# SERVICES_1.net
KiCad netlist of a schematic drawn in EAGLE
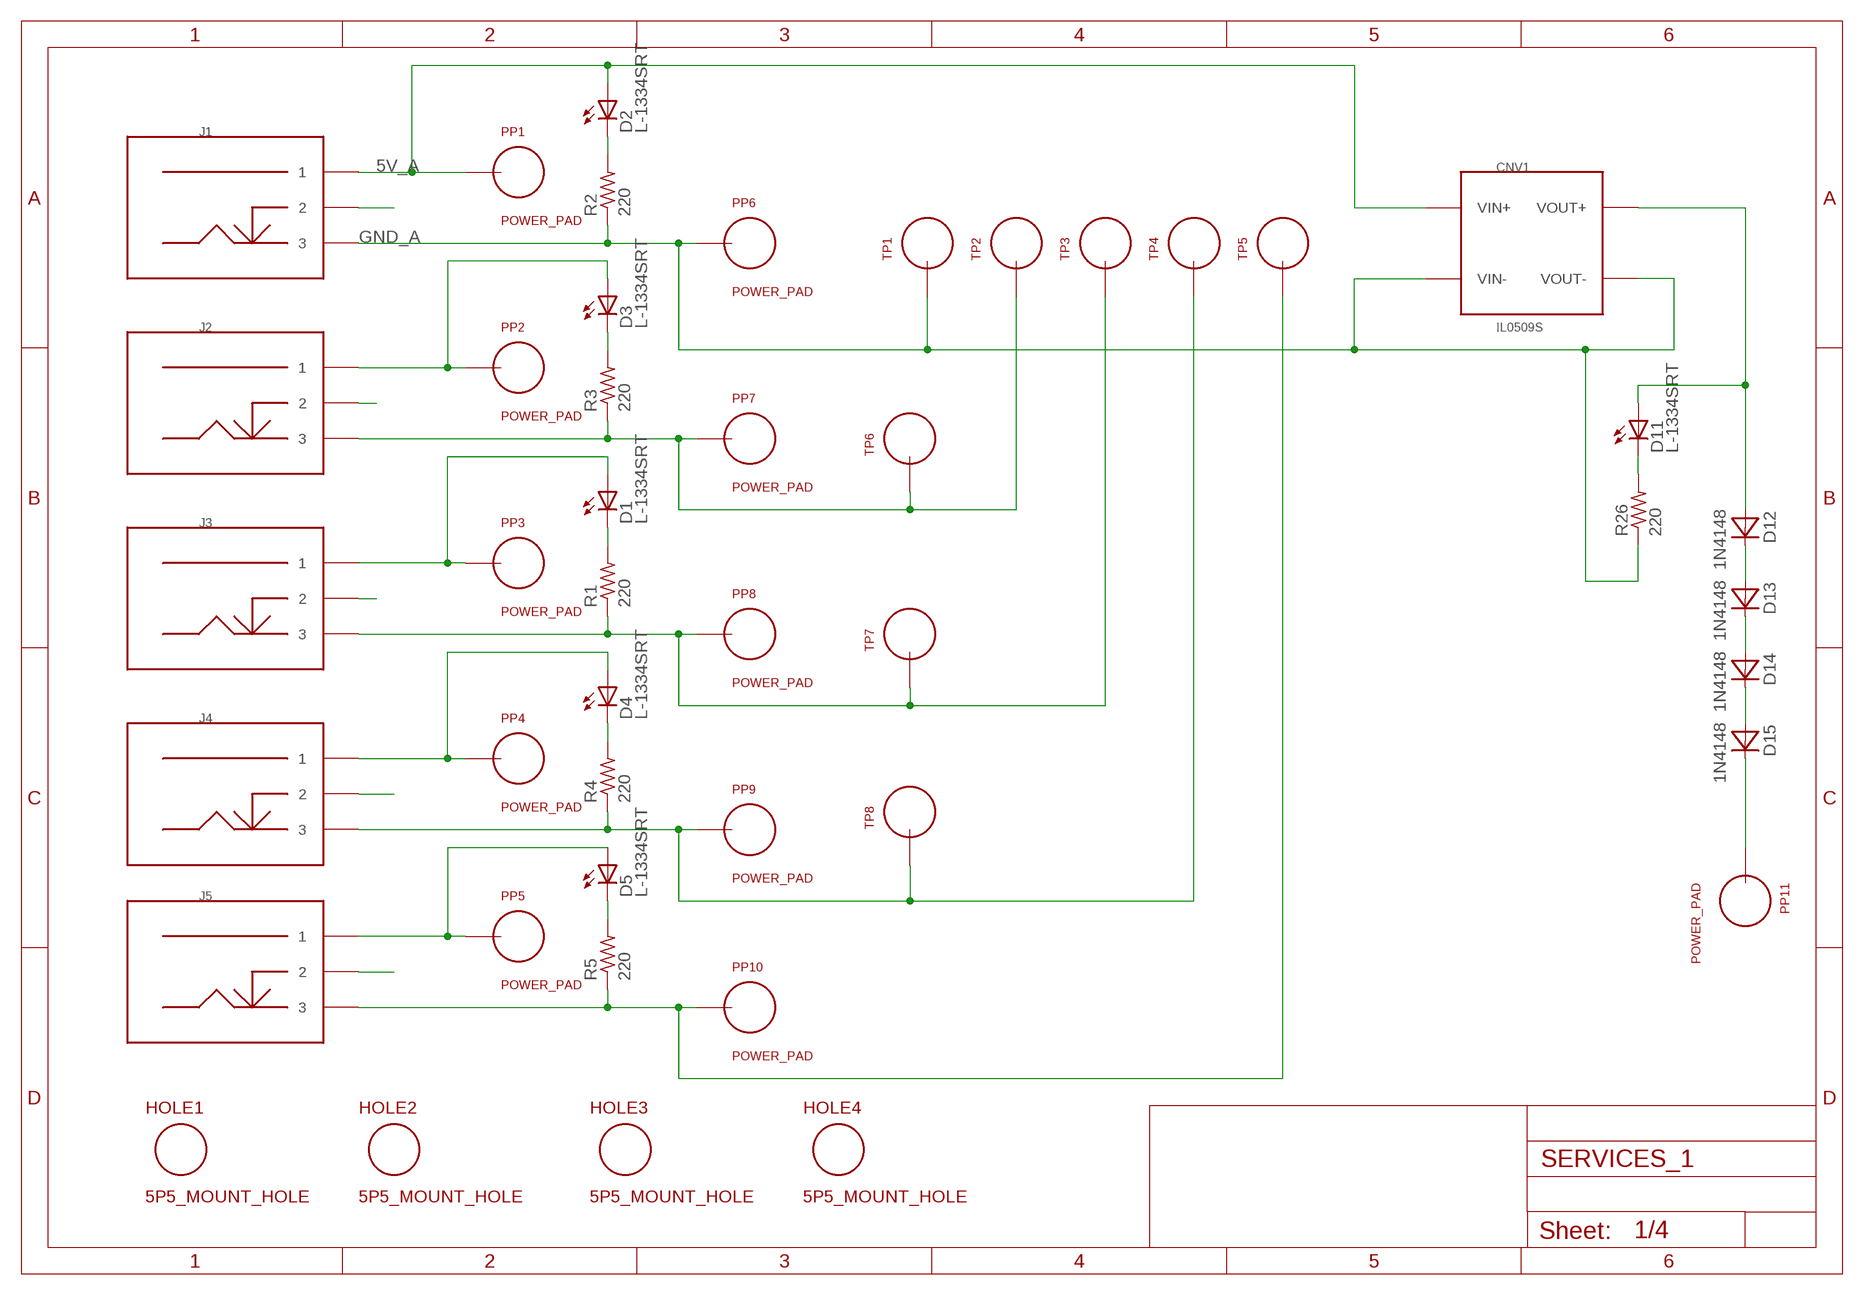
[diagram p0: schematic, sheet 1]
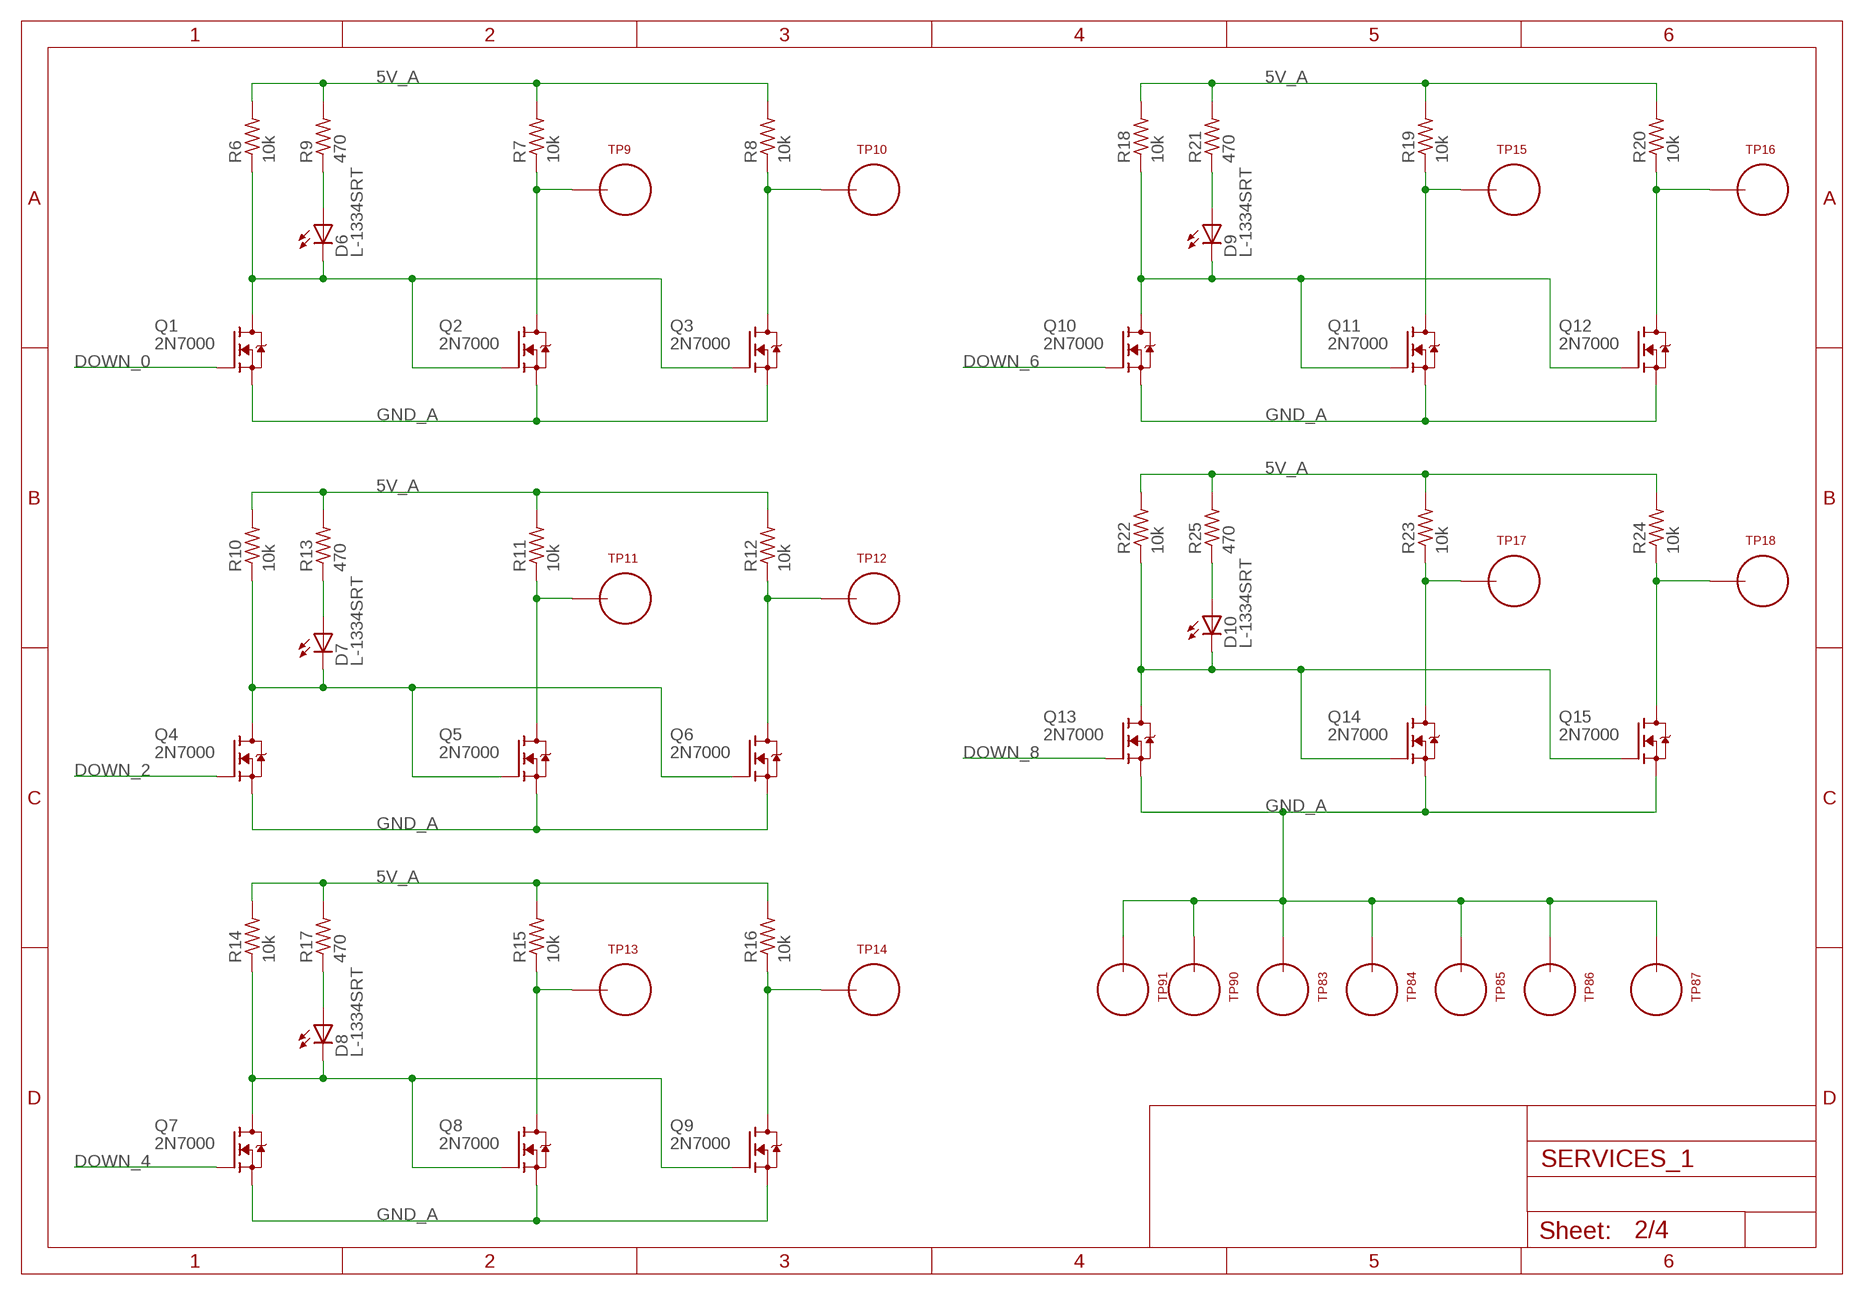
[diagram p1: schematic, sheet 2]
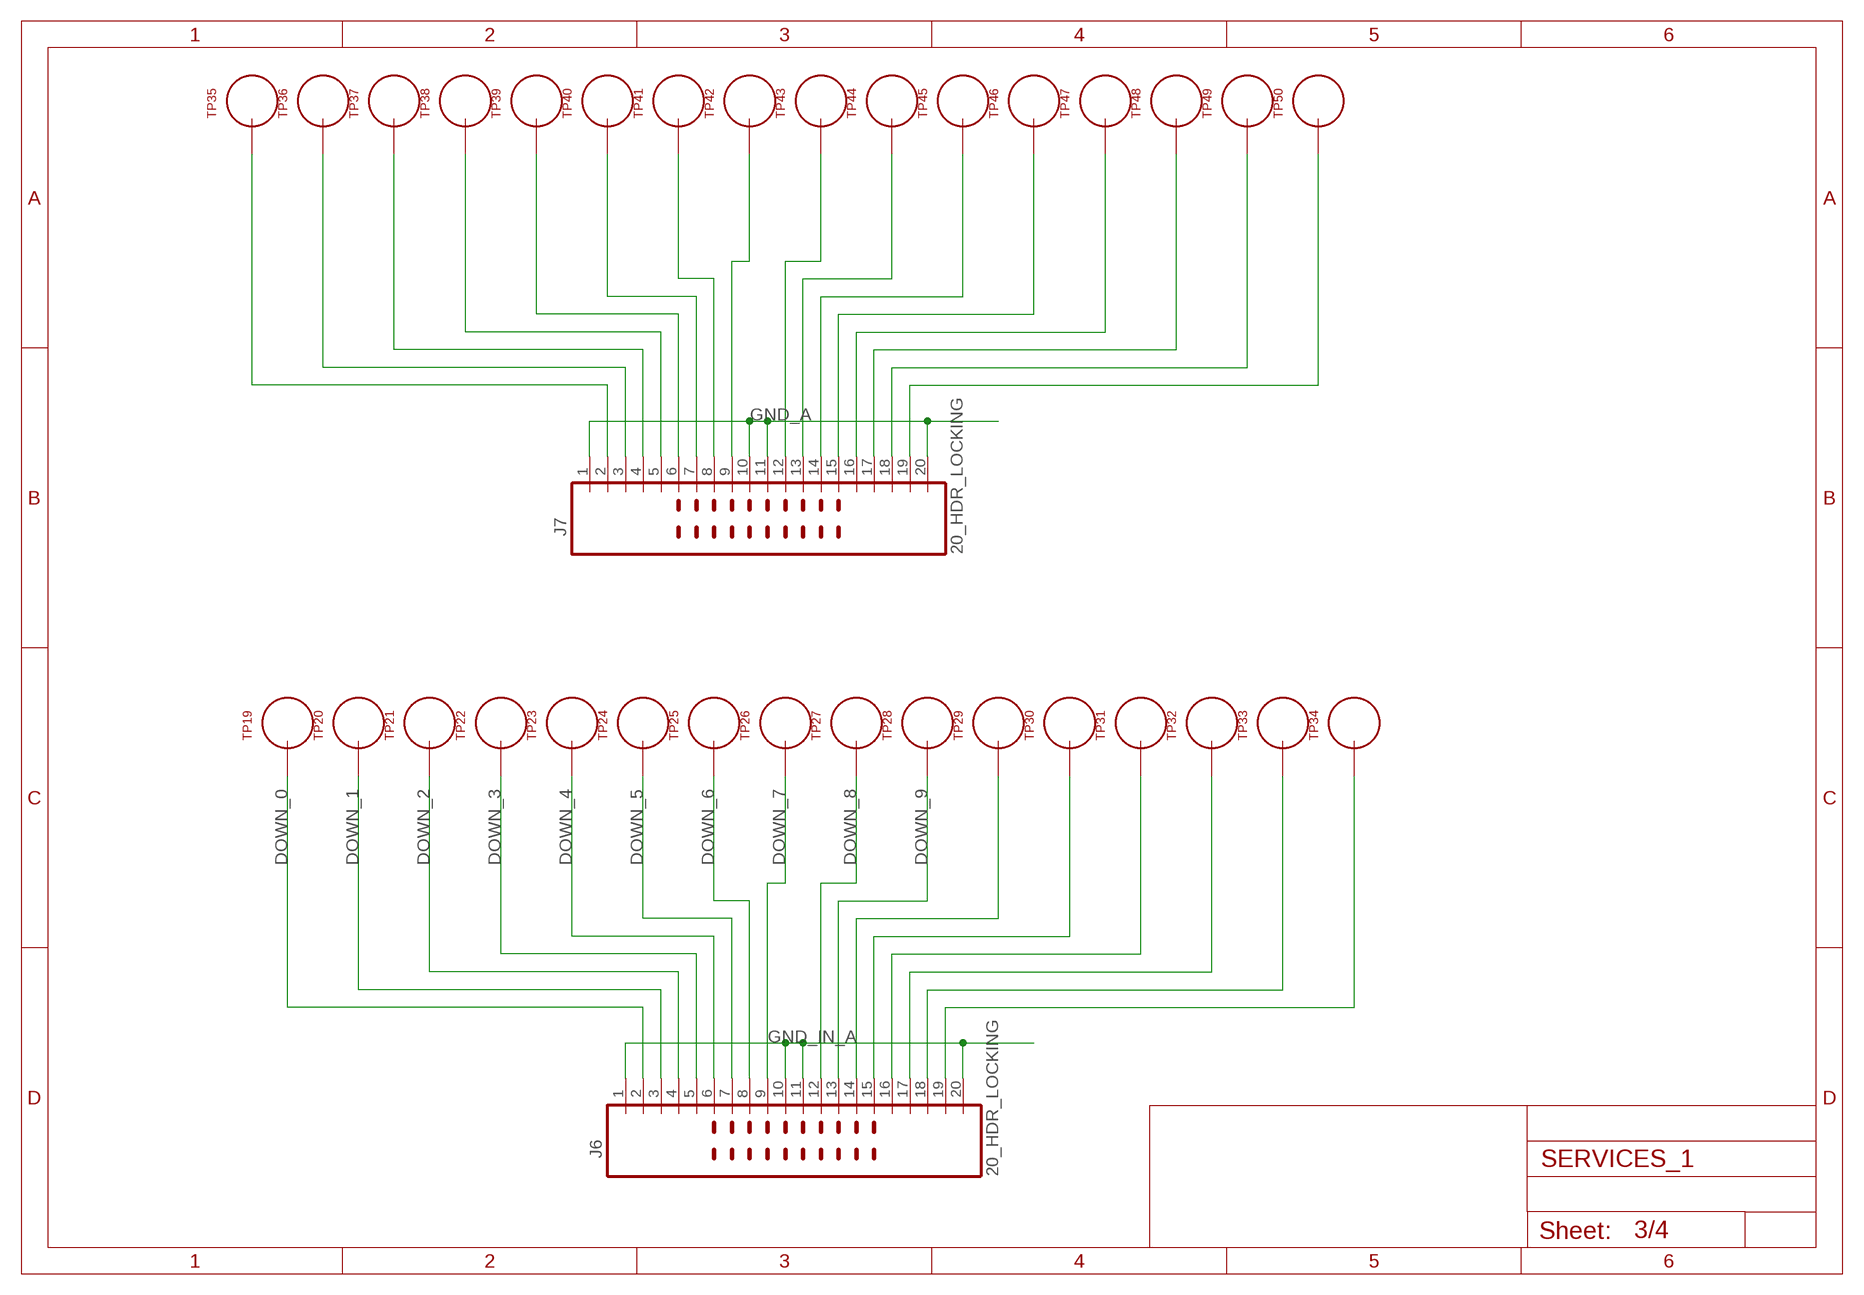
[diagram p2: schematic, sheet 3]
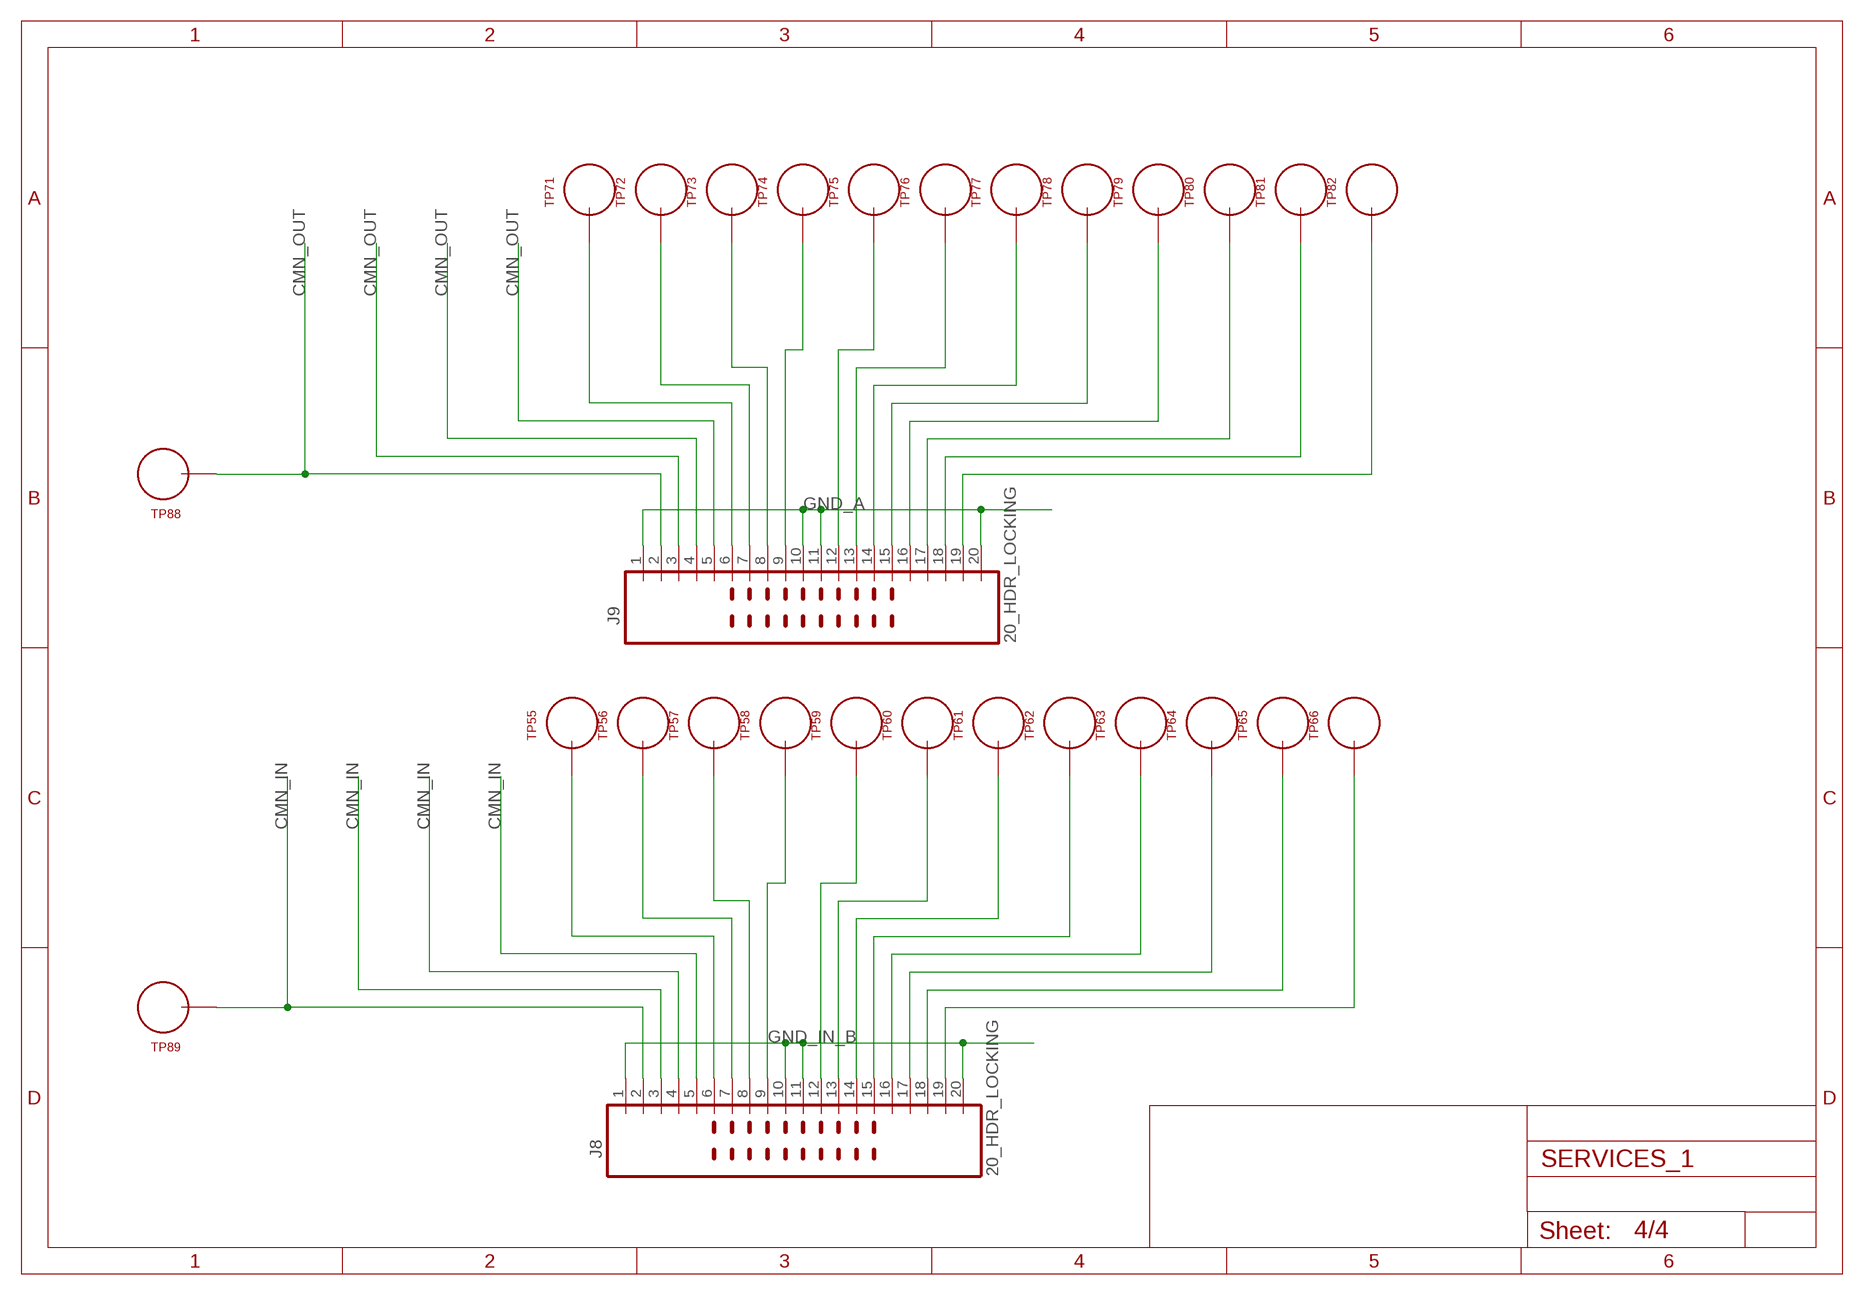
[diagram p3: schematic, sheet 4]

(export (version "E")
  (design (tool "Eeschema 10.0.6"))
  (components
    (comp (ref "D6")
      (value "L-1334SRT")
      (footprint "eagle-import:LED3MM")
      (libsource (lib "eagle-import") (part "L-1334SRT"))
    )
    (comp (ref "D7")
      (value "L-1334SRT")
      (footprint "eagle-import:LED3MM")
      (libsource (lib "eagle-import") (part "L-1334SRT"))
    )
    (comp (ref "D8")
      (value "L-1334SRT")
      (footprint "eagle-import:LED3MM")
      (libsource (lib "eagle-import") (part "L-1334SRT"))
    )
    (comp (ref "D9")
      (value "L-1334SRT")
      (footprint "eagle-import:LED3MM")
      (libsource (lib "eagle-import") (part "L-1334SRT"))
    )
    (comp (ref "D10")
      (value "L-1334SRT")
      (footprint "eagle-import:LED3MM")
      (libsource (lib "eagle-import") (part "L-1334SRT"))
    )
    (comp (ref "Q1")
      (value "2N7000")
      (footprint "eagle-import:TO92-DGS")
      (libsource (lib "eagle-import") (part "2N7000"))
    )
    (comp (ref "Q2")
      (value "2N7000")
      (footprint "eagle-import:TO92-DGS")
      (libsource (lib "eagle-import") (part "2N7000"))
    )
    (comp (ref "Q3")
      (value "2N7000")
      (footprint "eagle-import:TO92-DGS")
      (libsource (lib "eagle-import") (part "2N7000"))
    )
    (comp (ref "Q4")
      (value "2N7000")
      (footprint "eagle-import:TO92-DGS")
      (libsource (lib "eagle-import") (part "2N7000"))
    )
    (comp (ref "Q5")
      (value "2N7000")
      (footprint "eagle-import:TO92-DGS")
      (libsource (lib "eagle-import") (part "2N7000"))
    )
    (comp (ref "Q6")
      (value "2N7000")
      (footprint "eagle-import:TO92-DGS")
      (libsource (lib "eagle-import") (part "2N7000"))
    )
    (comp (ref "Q7")
      (value "2N7000")
      (footprint "eagle-import:TO92-DGS")
      (libsource (lib "eagle-import") (part "2N7000"))
    )
    (comp (ref "Q8")
      (value "2N7000")
      (footprint "eagle-import:TO92-DGS")
      (libsource (lib "eagle-import") (part "2N7000"))
    )
    (comp (ref "Q9")
      (value "2N7000")
      (footprint "eagle-import:TO92-DGS")
      (libsource (lib "eagle-import") (part "2N7000"))
    )
    (comp (ref "Q10")
      (value "2N7000")
      (footprint "eagle-import:TO92-DGS")
      (libsource (lib "eagle-import") (part "2N7000"))
    )
    (comp (ref "Q11")
      (value "2N7000")
      (footprint "eagle-import:TO92-DGS")
      (libsource (lib "eagle-import") (part "2N7000"))
    )
    (comp (ref "Q12")
      (value "2N7000")
      (footprint "eagle-import:TO92-DGS")
      (libsource (lib "eagle-import") (part "2N7000"))
    )
    (comp (ref "Q13")
      (value "2N7000")
      (footprint "eagle-import:TO92-DGS")
      (libsource (lib "eagle-import") (part "2N7000"))
    )
    (comp (ref "Q14")
      (value "2N7000")
      (footprint "eagle-import:TO92-DGS")
      (libsource (lib "eagle-import") (part "2N7000"))
    )
    (comp (ref "Q15")
      (value "2N7000")
      (footprint "eagle-import:TO92-DGS")
      (libsource (lib "eagle-import") (part "2N7000"))
    )
    (comp (ref "R6")
      (value "10k")
      (footprint "eagle-import:R_P2INCH")
      (libsource (lib "eagle-import") (part "R_P2INCH"))
    )
    (comp (ref "R7")
      (value "10k")
      (footprint "eagle-import:R_P2INCH")
      (libsource (lib "eagle-import") (part "R_P2INCH"))
    )
    (comp (ref "R8")
      (value "10k")
      (footprint "eagle-import:R_P2INCH")
      (libsource (lib "eagle-import") (part "R_P2INCH"))
    )
    (comp (ref "R9")
      (value "470")
      (footprint "eagle-import:R_P2INCH")
      (libsource (lib "eagle-import") (part "R_P2INCH"))
    )
    (comp (ref "R10")
      (value "10k")
      (footprint "eagle-import:R_P2INCH")
      (libsource (lib "eagle-import") (part "R_P2INCH"))
    )
    (comp (ref "R11")
      (value "10k")
      (footprint "eagle-import:R_P2INCH")
      (libsource (lib "eagle-import") (part "R_P2INCH"))
    )
    (comp (ref "R12")
      (value "10k")
      (footprint "eagle-import:R_P2INCH")
      (libsource (lib "eagle-import") (part "R_P2INCH"))
    )
    (comp (ref "R13")
      (value "470")
      (footprint "eagle-import:R_P2INCH")
      (libsource (lib "eagle-import") (part "R_P2INCH"))
    )
    (comp (ref "R14")
      (value "10k")
      (footprint "eagle-import:R_P2INCH")
      (libsource (lib "eagle-import") (part "R_P2INCH"))
    )
    (comp (ref "R15")
      (value "10k")
      (footprint "eagle-import:R_P2INCH")
      (libsource (lib "eagle-import") (part "R_P2INCH"))
    )
    (comp (ref "R16")
      (value "10k")
      (footprint "eagle-import:R_P2INCH")
      (libsource (lib "eagle-import") (part "R_P2INCH"))
    )
    (comp (ref "R17")
      (value "470")
      (footprint "eagle-import:R_P2INCH")
      (libsource (lib "eagle-import") (part "R_P2INCH"))
    )
    (comp (ref "R18")
      (value "10k")
      (footprint "eagle-import:R_P2INCH")
      (libsource (lib "eagle-import") (part "R_P2INCH"))
    )
    (comp (ref "R19")
      (value "10k")
      (footprint "eagle-import:R_P2INCH")
      (libsource (lib "eagle-import") (part "R_P2INCH"))
    )
    (comp (ref "R20")
      (value "10k")
      (footprint "eagle-import:R_P2INCH")
      (libsource (lib "eagle-import") (part "R_P2INCH"))
    )
    (comp (ref "R21")
      (value "470")
      (footprint "eagle-import:R_P2INCH")
      (libsource (lib "eagle-import") (part "R_P2INCH"))
    )
    (comp (ref "R22")
      (value "10k")
      (footprint "eagle-import:R_P2INCH")
      (libsource (lib "eagle-import") (part "R_P2INCH"))
    )
    (comp (ref "R23")
      (value "10k")
      (footprint "eagle-import:R_P2INCH")
      (libsource (lib "eagle-import") (part "R_P2INCH"))
    )
    (comp (ref "R24")
      (value "10k")
      (footprint "eagle-import:R_P2INCH")
      (libsource (lib "eagle-import") (part "R_P2INCH"))
    )
    (comp (ref "R25")
      (value "470")
      (footprint "eagle-import:R_P2INCH")
      (libsource (lib "eagle-import") (part "R_P2INCH"))
    )
    (comp (ref "TP9")
      (value "TEST_LOOP")
      (footprint "eagle-import:TEST_LOOP")
      (libsource (lib "eagle-import") (part "TEST_LOOP"))
    )
    (comp (ref "TP10")
      (value "TEST_LOOP")
      (footprint "eagle-import:TEST_LOOP")
      (libsource (lib "eagle-import") (part "TEST_LOOP"))
    )
    (comp (ref "TP11")
      (value "TEST_LOOP")
      (footprint "eagle-import:TEST_LOOP")
      (libsource (lib "eagle-import") (part "TEST_LOOP"))
    )
    (comp (ref "TP12")
      (value "TEST_LOOP")
      (footprint "eagle-import:TEST_LOOP")
      (libsource (lib "eagle-import") (part "TEST_LOOP"))
    )
    (comp (ref "TP13")
      (value "TEST_LOOP")
      (footprint "eagle-import:TEST_LOOP")
      (libsource (lib "eagle-import") (part "TEST_LOOP"))
    )
    (comp (ref "TP14")
      (value "TEST_LOOP")
      (footprint "eagle-import:TEST_LOOP")
      (libsource (lib "eagle-import") (part "TEST_LOOP"))
    )
    (comp (ref "TP15")
      (value "TEST_LOOP")
      (footprint "eagle-import:TEST_LOOP")
      (libsource (lib "eagle-import") (part "TEST_LOOP"))
    )
    (comp (ref "TP16")
      (value "TEST_LOOP")
      (footprint "eagle-import:TEST_LOOP")
      (libsource (lib "eagle-import") (part "TEST_LOOP"))
    )
    (comp (ref "TP17")
      (value "TEST_LOOP")
      (footprint "eagle-import:TEST_LOOP")
      (libsource (lib "eagle-import") (part "TEST_LOOP"))
    )
    (comp (ref "TP18")
      (value "TEST_LOOP")
      (footprint "eagle-import:TEST_LOOP")
      (libsource (lib "eagle-import") (part "TEST_LOOP"))
    )
    (comp (ref "TP83")
      (value "TEST_LOOP")
      (footprint "eagle-import:TEST_LOOP")
      (libsource (lib "eagle-import") (part "TEST_LOOP"))
    )
    (comp (ref "TP84")
      (value "TEST_LOOP")
      (footprint "eagle-import:TEST_LOOP")
      (libsource (lib "eagle-import") (part "TEST_LOOP"))
    )
    (comp (ref "TP85")
      (value "TEST_LOOP")
      (footprint "eagle-import:TEST_LOOP")
      (libsource (lib "eagle-import") (part "TEST_LOOP"))
    )
    (comp (ref "TP86")
      (value "TEST_LOOP")
      (footprint "eagle-import:TEST_LOOP")
      (libsource (lib "eagle-import") (part "TEST_LOOP"))
    )
    (comp (ref "TP87")
      (value "TEST_LOOP")
      (footprint "eagle-import:TEST_LOOP")
      (libsource (lib "eagle-import") (part "TEST_LOOP"))
    )
    (comp (ref "TP90")
      (value "TEST_LOOP")
      (footprint "eagle-import:TEST_LOOP")
      (libsource (lib "eagle-import") (part "TEST_LOOP"))
    )
    (comp (ref "TP91")
      (value "TEST_LOOP")
      (footprint "eagle-import:TEST_LOOP")
      (libsource (lib "eagle-import") (part "TEST_LOOP"))
    )
    (comp (ref "J8")
      (value "20_HDR_LOCKING")
      (footprint "eagle-import:20_HDR_LOCKING")
      (libsource (lib "eagle-import") (part "20_HDR_LOCKING"))
    )
    (comp (ref "J9")
      (value "20_HDR_LOCKING")
      (footprint "eagle-import:20_HDR_LOCKING")
      (libsource (lib "eagle-import") (part "20_HDR_LOCKING"))
    )
    (comp (ref "TP55")
      (value "TEST_LOOP")
      (footprint "eagle-import:TEST_LOOP")
      (libsource (lib "eagle-import") (part "TEST_LOOP"))
    )
    (comp (ref "TP56")
      (value "TEST_LOOP")
      (footprint "eagle-import:TEST_LOOP")
      (libsource (lib "eagle-import") (part "TEST_LOOP"))
    )
    (comp (ref "TP57")
      (value "TEST_LOOP")
      (footprint "eagle-import:TEST_LOOP")
      (libsource (lib "eagle-import") (part "TEST_LOOP"))
    )
    (comp (ref "TP58")
      (value "TEST_LOOP")
      (footprint "eagle-import:TEST_LOOP")
      (libsource (lib "eagle-import") (part "TEST_LOOP"))
    )
    (comp (ref "TP59")
      (value "TEST_LOOP")
      (footprint "eagle-import:TEST_LOOP")
      (libsource (lib "eagle-import") (part "TEST_LOOP"))
    )
    (comp (ref "TP60")
      (value "TEST_LOOP")
      (footprint "eagle-import:TEST_LOOP")
      (libsource (lib "eagle-import") (part "TEST_LOOP"))
    )
    (comp (ref "TP61")
      (value "TEST_LOOP")
      (footprint "eagle-import:TEST_LOOP")
      (libsource (lib "eagle-import") (part "TEST_LOOP"))
    )
    (comp (ref "TP62")
      (value "TEST_LOOP")
      (footprint "eagle-import:TEST_LOOP")
      (libsource (lib "eagle-import") (part "TEST_LOOP"))
    )
    (comp (ref "TP63")
      (value "TEST_LOOP")
      (footprint "eagle-import:TEST_LOOP")
      (libsource (lib "eagle-import") (part "TEST_LOOP"))
    )
    (comp (ref "TP64")
      (value "TEST_LOOP")
      (footprint "eagle-import:TEST_LOOP")
      (libsource (lib "eagle-import") (part "TEST_LOOP"))
    )
    (comp (ref "TP65")
      (value "TEST_LOOP")
      (footprint "eagle-import:TEST_LOOP")
      (libsource (lib "eagle-import") (part "TEST_LOOP"))
    )
    (comp (ref "TP66")
      (value "TEST_LOOP")
      (footprint "eagle-import:TEST_LOOP")
      (libsource (lib "eagle-import") (part "TEST_LOOP"))
    )
    (comp (ref "TP71")
      (value "TEST_LOOP")
      (footprint "eagle-import:TEST_LOOP")
      (libsource (lib "eagle-import") (part "TEST_LOOP"))
    )
    (comp (ref "TP72")
      (value "TEST_LOOP")
      (footprint "eagle-import:TEST_LOOP")
      (libsource (lib "eagle-import") (part "TEST_LOOP"))
    )
    (comp (ref "TP73")
      (value "TEST_LOOP")
      (footprint "eagle-import:TEST_LOOP")
      (libsource (lib "eagle-import") (part "TEST_LOOP"))
    )
    (comp (ref "TP74")
      (value "TEST_LOOP")
      (footprint "eagle-import:TEST_LOOP")
      (libsource (lib "eagle-import") (part "TEST_LOOP"))
    )
    (comp (ref "TP75")
      (value "TEST_LOOP")
      (footprint "eagle-import:TEST_LOOP")
      (libsource (lib "eagle-import") (part "TEST_LOOP"))
    )
    (comp (ref "TP76")
      (value "TEST_LOOP")
      (footprint "eagle-import:TEST_LOOP")
      (libsource (lib "eagle-import") (part "TEST_LOOP"))
    )
    (comp (ref "TP77")
      (value "TEST_LOOP")
      (footprint "eagle-import:TEST_LOOP")
      (libsource (lib "eagle-import") (part "TEST_LOOP"))
    )
    (comp (ref "TP78")
      (value "TEST_LOOP")
      (footprint "eagle-import:TEST_LOOP")
      (libsource (lib "eagle-import") (part "TEST_LOOP"))
    )
    (comp (ref "TP79")
      (value "TEST_LOOP")
      (footprint "eagle-import:TEST_LOOP")
      (libsource (lib "eagle-import") (part "TEST_LOOP"))
    )
    (comp (ref "TP80")
      (value "TEST_LOOP")
      (footprint "eagle-import:TEST_LOOP")
      (libsource (lib "eagle-import") (part "TEST_LOOP"))
    )
    (comp (ref "TP81")
      (value "TEST_LOOP")
      (footprint "eagle-import:TEST_LOOP")
      (libsource (lib "eagle-import") (part "TEST_LOOP"))
    )
    (comp (ref "TP82")
      (value "TEST_LOOP")
      (footprint "eagle-import:TEST_LOOP")
      (libsource (lib "eagle-import") (part "TEST_LOOP"))
    )
    (comp (ref "TP88")
      (value "TEST_LOOP")
      (footprint "eagle-import:TEST_LOOP")
      (libsource (lib "eagle-import") (part "TEST_LOOP"))
    )
    (comp (ref "TP89")
      (value "TEST_LOOP")
      (footprint "eagle-import:TEST_LOOP")
      (libsource (lib "eagle-import") (part "TEST_LOOP"))
    )
    (comp (ref "CNV1")
      (value "IL0509S")
      (footprint "eagle-import:SIL_IL")
      (libsource (lib "eagle-import") (part "IL0509S"))
    )
    (comp (ref "D1")
      (value "L-1334SRT")
      (footprint "eagle-import:LED3MM")
      (libsource (lib "eagle-import") (part "L-1334SRT"))
    )
    (comp (ref "D2")
      (value "L-1334SRT")
      (footprint "eagle-import:LED3MM")
      (libsource (lib "eagle-import") (part "L-1334SRT"))
    )
    (comp (ref "D3")
      (value "L-1334SRT")
      (footprint "eagle-import:LED3MM")
      (libsource (lib "eagle-import") (part "L-1334SRT"))
    )
    (comp (ref "D4")
      (value "L-1334SRT")
      (footprint "eagle-import:LED3MM")
      (libsource (lib "eagle-import") (part "L-1334SRT"))
    )
    (comp (ref "D5")
      (value "L-1334SRT")
      (footprint "eagle-import:LED3MM")
      (libsource (lib "eagle-import") (part "L-1334SRT"))
    )
    (comp (ref "D11")
      (value "L-1334SRT")
      (footprint "eagle-import:LED3MM")
      (libsource (lib "eagle-import") (part "L-1334SRT"))
    )
    (comp (ref "D12")
      (value "1N4148")
      (footprint "eagle-import:DO34-5")
      (libsource (lib "eagle-import") (part "1N4148"))
    )
    (comp (ref "D13")
      (value "1N4148")
      (footprint "eagle-import:DO34-5")
      (libsource (lib "eagle-import") (part "1N4148"))
    )
    (comp (ref "D14")
      (value "1N4148")
      (footprint "eagle-import:DO34-5")
      (libsource (lib "eagle-import") (part "1N4148"))
    )
    (comp (ref "D15")
      (value "1N4148")
      (footprint "eagle-import:DO34-5")
      (libsource (lib "eagle-import") (part "1N4148"))
    )
    (comp (ref "HOLE1")
      (value "5P5_MOUNT_HOLE")
      (footprint "eagle-import:5P5M_HOLE")
      (libsource (lib "eagle-import") (part "5P5_MOUNT_HOLE"))
    )
    (comp (ref "HOLE2")
      (value "5P5_MOUNT_HOLE")
      (footprint "eagle-import:5P5M_HOLE")
      (libsource (lib "eagle-import") (part "5P5_MOUNT_HOLE"))
    )
    (comp (ref "HOLE3")
      (value "5P5_MOUNT_HOLE")
      (footprint "eagle-import:5P5M_HOLE")
      (libsource (lib "eagle-import") (part "5P5_MOUNT_HOLE"))
    )
    (comp (ref "HOLE4")
      (value "5P5_MOUNT_HOLE")
      (footprint "eagle-import:5P5M_HOLE")
      (libsource (lib "eagle-import") (part "5P5_MOUNT_HOLE"))
    )
    (comp (ref "J1")
      (value "POWER_ENTRY")
      (footprint "eagle-import:POWER_25")
      (libsource (lib "eagle-import") (part "POWER_ENTRY"))
    )
    (comp (ref "J2")
      (value "POWER_ENTRY")
      (footprint "eagle-import:POWER_25")
      (libsource (lib "eagle-import") (part "POWER_ENTRY"))
    )
    (comp (ref "J3")
      (value "POWER_ENTRY")
      (footprint "eagle-import:POWER_25")
      (libsource (lib "eagle-import") (part "POWER_ENTRY"))
    )
    (comp (ref "J4")
      (value "POWER_ENTRY")
      (footprint "eagle-import:POWER_25")
      (libsource (lib "eagle-import") (part "POWER_ENTRY"))
    )
    (comp (ref "J5")
      (value "POWER_ENTRY")
      (footprint "eagle-import:POWER_25")
      (libsource (lib "eagle-import") (part "POWER_ENTRY"))
    )
    (comp (ref "PP1")
      (value "POWER_PAD")
      (footprint "eagle-import:POWER_PAD")
      (libsource (lib "eagle-import") (part "POWER_PAD"))
    )
    (comp (ref "PP2")
      (value "POWER_PAD")
      (footprint "eagle-import:POWER_PAD")
      (libsource (lib "eagle-import") (part "POWER_PAD"))
    )
    (comp (ref "PP3")
      (value "POWER_PAD")
      (footprint "eagle-import:POWER_PAD")
      (libsource (lib "eagle-import") (part "POWER_PAD"))
    )
    (comp (ref "PP4")
      (value "POWER_PAD")
      (footprint "eagle-import:POWER_PAD")
      (libsource (lib "eagle-import") (part "POWER_PAD"))
    )
    (comp (ref "PP5")
      (value "POWER_PAD")
      (footprint "eagle-import:POWER_PAD")
      (libsource (lib "eagle-import") (part "POWER_PAD"))
    )
    (comp (ref "PP6")
      (value "POWER_PAD")
      (footprint "eagle-import:POWER_PAD")
      (libsource (lib "eagle-import") (part "POWER_PAD"))
    )
    (comp (ref "PP7")
      (value "POWER_PAD")
      (footprint "eagle-import:POWER_PAD")
      (libsource (lib "eagle-import") (part "POWER_PAD"))
    )
    (comp (ref "PP8")
      (value "POWER_PAD")
      (footprint "eagle-import:POWER_PAD")
      (libsource (lib "eagle-import") (part "POWER_PAD"))
    )
    (comp (ref "PP9")
      (value "POWER_PAD")
      (footprint "eagle-import:POWER_PAD")
      (libsource (lib "eagle-import") (part "POWER_PAD"))
    )
    (comp (ref "PP10")
      (value "POWER_PAD")
      (footprint "eagle-import:POWER_PAD")
      (libsource (lib "eagle-import") (part "POWER_PAD"))
    )
    (comp (ref "PP11")
      (value "POWER_PAD")
      (footprint "eagle-import:POWER_PAD")
      (libsource (lib "eagle-import") (part "POWER_PAD"))
    )
    (comp (ref "R1")
      (value "220")
      (footprint "eagle-import:R_P2INCH")
      (libsource (lib "eagle-import") (part "R_P2INCH"))
    )
    (comp (ref "R2")
      (value "220")
      (footprint "eagle-import:R_P2INCH")
      (libsource (lib "eagle-import") (part "R_P2INCH"))
    )
    (comp (ref "R3")
      (value "220")
      (footprint "eagle-import:R_P2INCH")
      (libsource (lib "eagle-import") (part "R_P2INCH"))
    )
    (comp (ref "R4")
      (value "220")
      (footprint "eagle-import:R_P2INCH")
      (libsource (lib "eagle-import") (part "R_P2INCH"))
    )
    (comp (ref "R5")
      (value "220")
      (footprint "eagle-import:R_P2INCH")
      (libsource (lib "eagle-import") (part "R_P2INCH"))
    )
    (comp (ref "R26")
      (value "220")
      (footprint "eagle-import:R_P2INCH")
      (libsource (lib "eagle-import") (part "R_P2INCH"))
    )
    (comp (ref "TP1")
      (value "TEST_LOOP")
      (footprint "eagle-import:TEST_LOOP")
      (libsource (lib "eagle-import") (part "TEST_LOOP"))
    )
    (comp (ref "TP2")
      (value "TEST_LOOP")
      (footprint "eagle-import:TEST_LOOP")
      (libsource (lib "eagle-import") (part "TEST_LOOP"))
    )
    (comp (ref "TP3")
      (value "TEST_LOOP")
      (footprint "eagle-import:TEST_LOOP")
      (libsource (lib "eagle-import") (part "TEST_LOOP"))
    )
    (comp (ref "TP4")
      (value "TEST_LOOP")
      (footprint "eagle-import:TEST_LOOP")
      (libsource (lib "eagle-import") (part "TEST_LOOP"))
    )
    (comp (ref "TP5")
      (value "TEST_LOOP")
      (footprint "eagle-import:TEST_LOOP")
      (libsource (lib "eagle-import") (part "TEST_LOOP"))
    )
    (comp (ref "TP6")
      (value "TEST_LOOP")
      (footprint "eagle-import:TEST_LOOP")
      (libsource (lib "eagle-import") (part "TEST_LOOP"))
    )
    (comp (ref "TP7")
      (value "TEST_LOOP")
      (footprint "eagle-import:TEST_LOOP")
      (libsource (lib "eagle-import") (part "TEST_LOOP"))
    )
    (comp (ref "TP8")
      (value "TEST_LOOP")
      (footprint "eagle-import:TEST_LOOP")
      (libsource (lib "eagle-import") (part "TEST_LOOP"))
    )
    (comp (ref "J6")
      (value "20_HDR_LOCKING")
      (footprint "eagle-import:20_HDR_LOCKING")
      (libsource (lib "eagle-import") (part "20_HDR_LOCKING"))
    )
    (comp (ref "J7")
      (value "20_HDR_LOCKING")
      (footprint "eagle-import:20_HDR_LOCKING")
      (libsource (lib "eagle-import") (part "20_HDR_LOCKING"))
    )
    (comp (ref "TP19")
      (value "TEST_LOOP")
      (footprint "eagle-import:TEST_LOOP")
      (libsource (lib "eagle-import") (part "TEST_LOOP"))
    )
    (comp (ref "TP20")
      (value "TEST_LOOP")
      (footprint "eagle-import:TEST_LOOP")
      (libsource (lib "eagle-import") (part "TEST_LOOP"))
    )
    (comp (ref "TP21")
      (value "TEST_LOOP")
      (footprint "eagle-import:TEST_LOOP")
      (libsource (lib "eagle-import") (part "TEST_LOOP"))
    )
    (comp (ref "TP22")
      (value "TEST_LOOP")
      (footprint "eagle-import:TEST_LOOP")
      (libsource (lib "eagle-import") (part "TEST_LOOP"))
    )
    (comp (ref "TP23")
      (value "TEST_LOOP")
      (footprint "eagle-import:TEST_LOOP")
      (libsource (lib "eagle-import") (part "TEST_LOOP"))
    )
    (comp (ref "TP24")
      (value "TEST_LOOP")
      (footprint "eagle-import:TEST_LOOP")
      (libsource (lib "eagle-import") (part "TEST_LOOP"))
    )
    (comp (ref "TP25")
      (value "TEST_LOOP")
      (footprint "eagle-import:TEST_LOOP")
      (libsource (lib "eagle-import") (part "TEST_LOOP"))
    )
    (comp (ref "TP26")
      (value "TEST_LOOP")
      (footprint "eagle-import:TEST_LOOP")
      (libsource (lib "eagle-import") (part "TEST_LOOP"))
    )
    (comp (ref "TP27")
      (value "TEST_LOOP")
      (footprint "eagle-import:TEST_LOOP")
      (libsource (lib "eagle-import") (part "TEST_LOOP"))
    )
    (comp (ref "TP28")
      (value "TEST_LOOP")
      (footprint "eagle-import:TEST_LOOP")
      (libsource (lib "eagle-import") (part "TEST_LOOP"))
    )
    (comp (ref "TP29")
      (value "TEST_LOOP")
      (footprint "eagle-import:TEST_LOOP")
      (libsource (lib "eagle-import") (part "TEST_LOOP"))
    )
    (comp (ref "TP30")
      (value "TEST_LOOP")
      (footprint "eagle-import:TEST_LOOP")
      (libsource (lib "eagle-import") (part "TEST_LOOP"))
    )
    (comp (ref "TP31")
      (value "TEST_LOOP")
      (footprint "eagle-import:TEST_LOOP")
      (libsource (lib "eagle-import") (part "TEST_LOOP"))
    )
    (comp (ref "TP32")
      (value "TEST_LOOP")
      (footprint "eagle-import:TEST_LOOP")
      (libsource (lib "eagle-import") (part "TEST_LOOP"))
    )
    (comp (ref "TP33")
      (value "TEST_LOOP")
      (footprint "eagle-import:TEST_LOOP")
      (libsource (lib "eagle-import") (part "TEST_LOOP"))
    )
    (comp (ref "TP34")
      (value "TEST_LOOP")
      (footprint "eagle-import:TEST_LOOP")
      (libsource (lib "eagle-import") (part "TEST_LOOP"))
    )
    (comp (ref "TP35")
      (value "TEST_LOOP")
      (footprint "eagle-import:TEST_LOOP")
      (libsource (lib "eagle-import") (part "TEST_LOOP"))
    )
    (comp (ref "TP36")
      (value "TEST_LOOP")
      (footprint "eagle-import:TEST_LOOP")
      (libsource (lib "eagle-import") (part "TEST_LOOP"))
    )
    (comp (ref "TP37")
      (value "TEST_LOOP")
      (footprint "eagle-import:TEST_LOOP")
      (libsource (lib "eagle-import") (part "TEST_LOOP"))
    )
    (comp (ref "TP38")
      (value "TEST_LOOP")
      (footprint "eagle-import:TEST_LOOP")
      (libsource (lib "eagle-import") (part "TEST_LOOP"))
    )
    (comp (ref "TP39")
      (value "TEST_LOOP")
      (footprint "eagle-import:TEST_LOOP")
      (libsource (lib "eagle-import") (part "TEST_LOOP"))
    )
    (comp (ref "TP40")
      (value "TEST_LOOP")
      (footprint "eagle-import:TEST_LOOP")
      (libsource (lib "eagle-import") (part "TEST_LOOP"))
    )
    (comp (ref "TP41")
      (value "TEST_LOOP")
      (footprint "eagle-import:TEST_LOOP")
      (libsource (lib "eagle-import") (part "TEST_LOOP"))
    )
    (comp (ref "TP42")
      (value "TEST_LOOP")
      (footprint "eagle-import:TEST_LOOP")
      (libsource (lib "eagle-import") (part "TEST_LOOP"))
    )
    (comp (ref "TP43")
      (value "TEST_LOOP")
      (footprint "eagle-import:TEST_LOOP")
      (libsource (lib "eagle-import") (part "TEST_LOOP"))
    )
    (comp (ref "TP44")
      (value "TEST_LOOP")
      (footprint "eagle-import:TEST_LOOP")
      (libsource (lib "eagle-import") (part "TEST_LOOP"))
    )
    (comp (ref "TP45")
      (value "TEST_LOOP")
      (footprint "eagle-import:TEST_LOOP")
      (libsource (lib "eagle-import") (part "TEST_LOOP"))
    )
    (comp (ref "TP46")
      (value "TEST_LOOP")
      (footprint "eagle-import:TEST_LOOP")
      (libsource (lib "eagle-import") (part "TEST_LOOP"))
    )
    (comp (ref "TP47")
      (value "TEST_LOOP")
      (footprint "eagle-import:TEST_LOOP")
      (libsource (lib "eagle-import") (part "TEST_LOOP"))
    )
    (comp (ref "TP48")
      (value "TEST_LOOP")
      (footprint "eagle-import:TEST_LOOP")
      (libsource (lib "eagle-import") (part "TEST_LOOP"))
    )
    (comp (ref "TP49")
      (value "TEST_LOOP")
      (footprint "eagle-import:TEST_LOOP")
      (libsource (lib "eagle-import") (part "TEST_LOOP"))
    )
    (comp (ref "TP50")
      (value "TEST_LOOP")
      (footprint "eagle-import:TEST_LOOP")
      (libsource (lib "eagle-import") (part "TEST_LOOP"))
    )
  )
  (nets
    (net (code "1") (name "5V_A") (class "Default")
      (node (ref "CNV1") (pin "VIN+") (pinfunction "VIN+_VIN+") (pintype "power_in"))
      (node (ref "D2") (pin "A") (pinfunction "A_A") (pintype "passive"))
      (node (ref "J1") (pin "1") (pinfunction "1_1") (pintype "power_in"))
      (node (ref "PP1") (pin "1") (pinfunction "P$1_1") (pintype "bidirectional"))
      (node (ref "R10") (pin "2") (pinfunction "2_2") (pintype "passive"))
      (node (ref "R11") (pin "2") (pinfunction "2_2") (pintype "passive"))
      (node (ref "R12") (pin "2") (pinfunction "2_2") (pintype "passive"))
      (node (ref "R13") (pin "2") (pinfunction "2_2") (pintype "passive"))
      (node (ref "R14") (pin "2") (pinfunction "2_2") (pintype "passive"))
      (node (ref "R15") (pin "2") (pinfunction "2_2") (pintype "passive"))
      (node (ref "R16") (pin "2") (pinfunction "2_2") (pintype "passive"))
      (node (ref "R17") (pin "2") (pinfunction "2_2") (pintype "passive"))
      (node (ref "R18") (pin "2") (pinfunction "2_2") (pintype "passive"))
      (node (ref "R19") (pin "2") (pinfunction "2_2") (pintype "passive"))
      (node (ref "R20") (pin "2") (pinfunction "2_2") (pintype "passive"))
      (node (ref "R21") (pin "2") (pinfunction "2_2") (pintype "passive"))
      (node (ref "R22") (pin "2") (pinfunction "2_2") (pintype "passive"))
      (node (ref "R23") (pin "2") (pinfunction "2_2") (pintype "passive"))
      (node (ref "R24") (pin "2") (pinfunction "2_2") (pintype "passive"))
      (node (ref "R25") (pin "2") (pinfunction "2_2") (pintype "passive"))
      (node (ref "R6") (pin "2") (pinfunction "2_2") (pintype "passive"))
      (node (ref "R7") (pin "2") (pinfunction "2_2") (pintype "passive"))
      (node (ref "R8") (pin "2") (pinfunction "2_2") (pintype "passive"))
      (node (ref "R9") (pin "2") (pinfunction "2_2") (pintype "passive"))
    )
    (net (code "2") (name "CMN_IN") (class "Default")
      (node (ref "J8") (pin "2") (pinfunction "2_2") (pintype "bidirectional"))
      (node (ref "J8") (pin "3") (pinfunction "3_3") (pintype "bidirectional"))
      (node (ref "J8") (pin "4") (pinfunction "4_4") (pintype "bidirectional"))
      (node (ref "J8") (pin "5") (pinfunction "5_5") (pintype "bidirectional"))
      (node (ref "TP89") (pin "P$1") (pinfunction "P$1_P$1") (pintype "bidirectional"))
    )
    (net (code "3") (name "CMN_OUT") (class "Default")
      (node (ref "J9") (pin "2") (pinfunction "2_2") (pintype "bidirectional"))
      (node (ref "J9") (pin "3") (pinfunction "3_3") (pintype "bidirectional"))
      (node (ref "J9") (pin "4") (pinfunction "4_4") (pintype "bidirectional"))
      (node (ref "J9") (pin "5") (pinfunction "5_5") (pintype "bidirectional"))
      (node (ref "TP88") (pin "P$1") (pinfunction "P$1_P$1") (pintype "bidirectional"))
    )
    (net (code "4") (name "DOWN_0") (class "Default")
      (node (ref "J6") (pin "2") (pinfunction "2_2") (pintype "bidirectional"))
      (node (ref "Q1") (pin "G") (pinfunction "G_G") (pintype "passive"))
      (node (ref "TP19") (pin "P$1") (pinfunction "P$1_P$1") (pintype "bidirectional"))
    )
    (net (code "5") (name "DOWN_1") (class "Default")
      (node (ref "J6") (pin "3") (pinfunction "3_3") (pintype "bidirectional"))
      (node (ref "TP20") (pin "P$1") (pinfunction "P$1_P$1") (pintype "bidirectional"))
    )
    (net (code "6") (name "DOWN_2") (class "Default")
      (node (ref "J6") (pin "4") (pinfunction "4_4") (pintype "bidirectional"))
      (node (ref "Q4") (pin "G") (pinfunction "G_G") (pintype "passive"))
      (node (ref "TP21") (pin "P$1") (pinfunction "P$1_P$1") (pintype "bidirectional"))
    )
    (net (code "7") (name "DOWN_3") (class "Default")
      (node (ref "J6") (pin "5") (pinfunction "5_5") (pintype "bidirectional"))
      (node (ref "TP22") (pin "P$1") (pinfunction "P$1_P$1") (pintype "bidirectional"))
    )
    (net (code "8") (name "DOWN_4") (class "Default")
      (node (ref "J6") (pin "6") (pinfunction "6_6") (pintype "bidirectional"))
      (node (ref "Q7") (pin "G") (pinfunction "G_G") (pintype "passive"))
      (node (ref "TP23") (pin "P$1") (pinfunction "P$1_P$1") (pintype "bidirectional"))
    )
    (net (code "9") (name "DOWN_5") (class "Default")
      (node (ref "J6") (pin "7") (pinfunction "7_7") (pintype "bidirectional"))
      (node (ref "TP24") (pin "P$1") (pinfunction "P$1_P$1") (pintype "bidirectional"))
    )
    (net (code "10") (name "DOWN_6") (class "Default")
      (node (ref "J6") (pin "8") (pinfunction "8_8") (pintype "bidirectional"))
      (node (ref "Q10") (pin "G") (pinfunction "G_G") (pintype "passive"))
      (node (ref "TP25") (pin "P$1") (pinfunction "P$1_P$1") (pintype "bidirectional"))
    )
    (net (code "11") (name "DOWN_7") (class "Default")
      (node (ref "J6") (pin "9") (pinfunction "9_9") (pintype "bidirectional"))
      (node (ref "TP26") (pin "P$1") (pinfunction "P$1_P$1") (pintype "bidirectional"))
    )
    (net (code "12") (name "DOWN_8") (class "Default")
      (node (ref "J6") (pin "12") (pinfunction "12_12") (pintype "bidirectional"))
      (node (ref "Q13") (pin "G") (pinfunction "G_G") (pintype "passive"))
      (node (ref "TP27") (pin "P$1") (pinfunction "P$1_P$1") (pintype "bidirectional"))
    )
    (net (code "13") (name "DOWN_9") (class "Default")
      (node (ref "J6") (pin "13") (pinfunction "13_13") (pintype "bidirectional"))
      (node (ref "TP28") (pin "P$1") (pinfunction "P$1_P$1") (pintype "bidirectional"))
    )
    (net (code "14") (name "GND_A") (class "Default")
      (node (ref "CNV1") (pin "VIN-") (pinfunction "VIN-_VIN-") (pintype "power_in"))
      (node (ref "CNV1") (pin "VOUT-") (pinfunction "VOUT-_VOUT-") (pintype "power_in"))
      (node (ref "J1") (pin "3") (pinfunction "3_3") (pintype "power_in"))
      (node (ref "J7") (pin "1") (pinfunction "1_1") (pintype "bidirectional"))
      (node (ref "J7") (pin "10") (pinfunction "10_10") (pintype "bidirectional"))
      (node (ref "J7") (pin "11") (pinfunction "11_11") (pintype "bidirectional"))
      (node (ref "J7") (pin "20") (pinfunction "20_20") (pintype "bidirectional"))
      (node (ref "J9") (pin "1") (pinfunction "1_1") (pintype "bidirectional"))
      (node (ref "J9") (pin "10") (pinfunction "10_10") (pintype "bidirectional"))
      (node (ref "J9") (pin "11") (pinfunction "11_11") (pintype "bidirectional"))
      (node (ref "J9") (pin "20") (pinfunction "20_20") (pintype "bidirectional"))
      (node (ref "PP6") (pin "1") (pinfunction "P$1_1") (pintype "bidirectional"))
      (node (ref "Q1") (pin "S") (pinfunction "S_S") (pintype "passive"))
      (node (ref "Q10") (pin "S") (pinfunction "S_S") (pintype "passive"))
      (node (ref "Q11") (pin "S") (pinfunction "S_S") (pintype "passive"))
      (node (ref "Q12") (pin "S") (pinfunction "S_S") (pintype "passive"))
      (node (ref "Q13") (pin "S") (pinfunction "S_S") (pintype "passive"))
      (node (ref "Q14") (pin "S") (pinfunction "S_S") (pintype "passive"))
      (node (ref "Q15") (pin "S") (pinfunction "S_S") (pintype "passive"))
      (node (ref "Q2") (pin "S") (pinfunction "S_S") (pintype "passive"))
      (node (ref "Q3") (pin "S") (pinfunction "S_S") (pintype "passive"))
      (node (ref "Q4") (pin "S") (pinfunction "S_S") (pintype "passive"))
      (node (ref "Q5") (pin "S") (pinfunction "S_S") (pintype "passive"))
      (node (ref "Q6") (pin "S") (pinfunction "S_S") (pintype "passive"))
      (node (ref "Q7") (pin "S") (pinfunction "S_S") (pintype "passive"))
      (node (ref "Q8") (pin "S") (pinfunction "S_S") (pintype "passive"))
      (node (ref "Q9") (pin "S") (pinfunction "S_S") (pintype "passive"))
      (node (ref "R2") (pin "1") (pinfunction "1_1") (pintype "passive"))
      (node (ref "R26") (pin "1") (pinfunction "1_1") (pintype "passive"))
      (node (ref "TP1") (pin "P$1") (pinfunction "P$1_P$1") (pintype "bidirectional"))
      (node (ref "TP83") (pin "P$1") (pinfunction "P$1_P$1") (pintype "bidirectional"))
      (node (ref "TP84") (pin "P$1") (pinfunction "P$1_P$1") (pintype "bidirectional"))
      (node (ref "TP85") (pin "P$1") (pinfunction "P$1_P$1") (pintype "bidirectional"))
      (node (ref "TP86") (pin "P$1") (pinfunction "P$1_P$1") (pintype "bidirectional"))
      (node (ref "TP87") (pin "P$1") (pinfunction "P$1_P$1") (pintype "bidirectional"))
      (node (ref "TP90") (pin "P$1") (pinfunction "P$1_P$1") (pintype "bidirectional"))
      (node (ref "TP91") (pin "P$1") (pinfunction "P$1_P$1") (pintype "bidirectional"))
    )
    (net (code "15") (name "GND_IN_A") (class "Default")
      (node (ref "J6") (pin "1") (pinfunction "1_1") (pintype "bidirectional"))
      (node (ref "J6") (pin "10") (pinfunction "10_10") (pintype "bidirectional"))
      (node (ref "J6") (pin "11") (pinfunction "11_11") (pintype "bidirectional"))
      (node (ref "J6") (pin "20") (pinfunction "20_20") (pintype "bidirectional"))
    )
    (net (code "16") (name "GND_IN_B") (class "Default")
      (node (ref "J8") (pin "1") (pinfunction "1_1") (pintype "bidirectional"))
      (node (ref "J8") (pin "10") (pinfunction "10_10") (pintype "bidirectional"))
      (node (ref "J8") (pin "11") (pinfunction "11_11") (pintype "bidirectional"))
      (node (ref "J8") (pin "20") (pinfunction "20_20") (pintype "bidirectional"))
    )
    (net (code "17") (name "Net-(CNV1-PadVOUT+)") (class "Default")
      (node (ref "CNV1") (pin "VOUT+") (pinfunction "VOUT+_VOUT+") (pintype "power_in"))
      (node (ref "D11") (pin "A") (pinfunction "A_A") (pintype "passive"))
      (node (ref "D12") (pin "A") (pinfunction "A_A") (pintype "passive"))
    )
    (net (code "18") (name "Net-(D1-C)") (class "Default")
      (node (ref "D1") (pin "K") (pinfunction "C_K") (pintype "passive"))
      (node (ref "R1") (pin "2") (pinfunction "2_2") (pintype "passive"))
    )
    (net (code "19") (name "Net-(D2-C)") (class "Default")
      (node (ref "D2") (pin "K") (pinfunction "C_K") (pintype "passive"))
      (node (ref "R2") (pin "2") (pinfunction "2_2") (pintype "passive"))
    )
    (net (code "20") (name "Net-(D3-C)") (class "Default")
      (node (ref "D3") (pin "K") (pinfunction "C_K") (pintype "passive"))
      (node (ref "R3") (pin "2") (pinfunction "2_2") (pintype "passive"))
    )
    (net (code "21") (name "Net-(D4-C)") (class "Default")
      (node (ref "D4") (pin "K") (pinfunction "C_K") (pintype "passive"))
      (node (ref "R4") (pin "2") (pinfunction "2_2") (pintype "passive"))
    )
    (net (code "22") (name "Net-(D5-C)") (class "Default")
      (node (ref "D5") (pin "K") (pinfunction "C_K") (pintype "passive"))
      (node (ref "R5") (pin "2") (pinfunction "2_2") (pintype "passive"))
    )
    (net (code "23") (name "Net-(D6-C)") (class "Default")
      (node (ref "D6") (pin "K") (pinfunction "C_K") (pintype "passive"))
      (node (ref "Q1") (pin "D") (pinfunction "D_D") (pintype "passive"))
      (node (ref "Q2") (pin "G") (pinfunction "G_G") (pintype "passive"))
      (node (ref "Q3") (pin "G") (pinfunction "G_G") (pintype "passive"))
      (node (ref "R6") (pin "1") (pinfunction "1_1") (pintype "passive"))
    )
    (net (code "24") (name "Net-(D6-PadA)") (class "Default")
      (node (ref "D6") (pin "A") (pinfunction "A_A") (pintype "passive"))
      (node (ref "R9") (pin "1") (pinfunction "1_1") (pintype "passive"))
    )
    (net (code "25") (name "Net-(D7-C)") (class "Default")
      (node (ref "D7") (pin "K") (pinfunction "C_K") (pintype "passive"))
      (node (ref "Q4") (pin "D") (pinfunction "D_D") (pintype "passive"))
      (node (ref "Q5") (pin "G") (pinfunction "G_G") (pintype "passive"))
      (node (ref "Q6") (pin "G") (pinfunction "G_G") (pintype "passive"))
      (node (ref "R10") (pin "1") (pinfunction "1_1") (pintype "passive"))
    )
    (net (code "26") (name "Net-(D7-PadA)") (class "Default")
      (node (ref "D7") (pin "A") (pinfunction "A_A") (pintype "passive"))
      (node (ref "R13") (pin "1") (pinfunction "1_1") (pintype "passive"))
    )
    (net (code "27") (name "Net-(D8-C)") (class "Default")
      (node (ref "D8") (pin "K") (pinfunction "C_K") (pintype "passive"))
      (node (ref "Q7") (pin "D") (pinfunction "D_D") (pintype "passive"))
      (node (ref "Q8") (pin "G") (pinfunction "G_G") (pintype "passive"))
      (node (ref "Q9") (pin "G") (pinfunction "G_G") (pintype "passive"))
      (node (ref "R14") (pin "1") (pinfunction "1_1") (pintype "passive"))
    )
    (net (code "28") (name "Net-(D8-PadA)") (class "Default")
      (node (ref "D8") (pin "A") (pinfunction "A_A") (pintype "passive"))
      (node (ref "R17") (pin "1") (pinfunction "1_1") (pintype "passive"))
    )
    (net (code "29") (name "Net-(D9-C)") (class "Default")
      (node (ref "D9") (pin "K") (pinfunction "C_K") (pintype "passive"))
      (node (ref "Q10") (pin "D") (pinfunction "D_D") (pintype "passive"))
      (node (ref "Q11") (pin "G") (pinfunction "G_G") (pintype "passive"))
      (node (ref "Q12") (pin "G") (pinfunction "G_G") (pintype "passive"))
      (node (ref "R18") (pin "1") (pinfunction "1_1") (pintype "passive"))
    )
    (net (code "30") (name "Net-(D9-PadA)") (class "Default")
      (node (ref "D9") (pin "A") (pinfunction "A_A") (pintype "passive"))
      (node (ref "R21") (pin "1") (pinfunction "1_1") (pintype "passive"))
    )
    (net (code "31") (name "Net-(D10-C)") (class "Default")
      (node (ref "D10") (pin "K") (pinfunction "C_K") (pintype "passive"))
      (node (ref "Q13") (pin "D") (pinfunction "D_D") (pintype "passive"))
      (node (ref "Q14") (pin "G") (pinfunction "G_G") (pintype "passive"))
      (node (ref "Q15") (pin "G") (pinfunction "G_G") (pintype "passive"))
      (node (ref "R22") (pin "1") (pinfunction "1_1") (pintype "passive"))
    )
    (net (code "32") (name "Net-(D10-PadA)") (class "Default")
      (node (ref "D10") (pin "A") (pinfunction "A_A") (pintype "passive"))
      (node (ref "R25") (pin "1") (pinfunction "1_1") (pintype "passive"))
    )
    (net (code "33") (name "Net-(D11-C)") (class "Default")
      (node (ref "D11") (pin "K") (pinfunction "C_K") (pintype "passive"))
      (node (ref "R26") (pin "2") (pinfunction "2_2") (pintype "passive"))
    )
    (net (code "34") (name "Net-(D12-PadC)") (class "Default")
      (node (ref "D12") (pin "C") (pinfunction "C_C") (pintype "passive"))
      (node (ref "D13") (pin "A") (pinfunction "A_A") (pintype "passive"))
    )
    (net (code "35") (name "Net-(D13-PadC)") (class "Default")
      (node (ref "D13") (pin "C") (pinfunction "C_C") (pintype "passive"))
      (node (ref "D14") (pin "A") (pinfunction "A_A") (pintype "passive"))
    )
    (net (code "36") (name "Net-(D14-PadC)") (class "Default")
      (node (ref "D14") (pin "C") (pinfunction "C_C") (pintype "passive"))
      (node (ref "D15") (pin "A") (pinfunction "A_A") (pintype "passive"))
    )
    (net (code "37") (name "Net-(J6-Pad14)") (class "Default")
      (node (ref "J6") (pin "14") (pinfunction "14_14") (pintype "bidirectional"))
      (node (ref "TP29") (pin "P$1") (pinfunction "P$1_P$1") (pintype "bidirectional"))
    )
    (net (code "38") (name "Net-(J6-Pad15)") (class "Default")
      (node (ref "J6") (pin "15") (pinfunction "15_15") (pintype "bidirectional"))
      (node (ref "TP30") (pin "P$1") (pinfunction "P$1_P$1") (pintype "bidirectional"))
    )
    (net (code "39") (name "Net-(J6-Pad16)") (class "Default")
      (node (ref "J6") (pin "16") (pinfunction "16_16") (pintype "bidirectional"))
      (node (ref "TP31") (pin "P$1") (pinfunction "P$1_P$1") (pintype "bidirectional"))
    )
    (net (code "40") (name "Net-(J6-Pad17)") (class "Default")
      (node (ref "J6") (pin "17") (pinfunction "17_17") (pintype "bidirectional"))
      (node (ref "TP32") (pin "P$1") (pinfunction "P$1_P$1") (pintype "bidirectional"))
    )
    (net (code "41") (name "Net-(J6-Pad18)") (class "Default")
      (node (ref "J6") (pin "18") (pinfunction "18_18") (pintype "bidirectional"))
      (node (ref "TP33") (pin "P$1") (pinfunction "P$1_P$1") (pintype "bidirectional"))
    )
    (net (code "42") (name "Net-(J6-Pad19)") (class "Default")
      (node (ref "J6") (pin "19") (pinfunction "19_19") (pintype "bidirectional"))
      (node (ref "TP34") (pin "P$1") (pinfunction "P$1_P$1") (pintype "bidirectional"))
    )
    (net (code "43") (name "Net-(J7-Pad2)") (class "Default")
      (node (ref "J7") (pin "2") (pinfunction "2_2") (pintype "bidirectional"))
      (node (ref "TP35") (pin "P$1") (pinfunction "P$1_P$1") (pintype "bidirectional"))
    )
    (net (code "44") (name "Net-(J7-Pad3)") (class "Default")
      (node (ref "J7") (pin "3") (pinfunction "3_3") (pintype "bidirectional"))
      (node (ref "TP36") (pin "P$1") (pinfunction "P$1_P$1") (pintype "bidirectional"))
    )
    (net (code "45") (name "Net-(J7-Pad4)") (class "Default")
      (node (ref "J7") (pin "4") (pinfunction "4_4") (pintype "bidirectional"))
      (node (ref "TP37") (pin "P$1") (pinfunction "P$1_P$1") (pintype "bidirectional"))
    )
    (net (code "46") (name "Net-(J7-Pad5)") (class "Default")
      (node (ref "J7") (pin "5") (pinfunction "5_5") (pintype "bidirectional"))
      (node (ref "TP38") (pin "P$1") (pinfunction "P$1_P$1") (pintype "bidirectional"))
    )
    (net (code "47") (name "Net-(J7-Pad6)") (class "Default")
      (node (ref "J7") (pin "6") (pinfunction "6_6") (pintype "bidirectional"))
      (node (ref "TP39") (pin "P$1") (pinfunction "P$1_P$1") (pintype "bidirectional"))
    )
    (net (code "48") (name "Net-(J7-Pad7)") (class "Default")
      (node (ref "J7") (pin "7") (pinfunction "7_7") (pintype "bidirectional"))
      (node (ref "TP40") (pin "P$1") (pinfunction "P$1_P$1") (pintype "bidirectional"))
    )
    (net (code "49") (name "Net-(J7-Pad8)") (class "Default")
      (node (ref "J7") (pin "8") (pinfunction "8_8") (pintype "bidirectional"))
      (node (ref "TP41") (pin "P$1") (pinfunction "P$1_P$1") (pintype "bidirectional"))
    )
    (net (code "50") (name "Net-(J7-Pad9)") (class "Default")
      (node (ref "J7") (pin "9") (pinfunction "9_9") (pintype "bidirectional"))
      (node (ref "TP42") (pin "P$1") (pinfunction "P$1_P$1") (pintype "bidirectional"))
    )
    (net (code "51") (name "Net-(J7-Pad12)") (class "Default")
      (node (ref "J7") (pin "12") (pinfunction "12_12") (pintype "bidirectional"))
      (node (ref "TP43") (pin "P$1") (pinfunction "P$1_P$1") (pintype "bidirectional"))
    )
    (net (code "52") (name "Net-(J7-Pad13)") (class "Default")
      (node (ref "J7") (pin "13") (pinfunction "13_13") (pintype "bidirectional"))
      (node (ref "TP44") (pin "P$1") (pinfunction "P$1_P$1") (pintype "bidirectional"))
    )
    (net (code "53") (name "Net-(J7-Pad14)") (class "Default")
      (node (ref "J7") (pin "14") (pinfunction "14_14") (pintype "bidirectional"))
      (node (ref "TP45") (pin "P$1") (pinfunction "P$1_P$1") (pintype "bidirectional"))
    )
    (net (code "54") (name "Net-(J7-Pad15)") (class "Default")
      (node (ref "J7") (pin "15") (pinfunction "15_15") (pintype "bidirectional"))
      (node (ref "TP46") (pin "P$1") (pinfunction "P$1_P$1") (pintype "bidirectional"))
    )
    (net (code "55") (name "Net-(J7-Pad16)") (class "Default")
      (node (ref "J7") (pin "16") (pinfunction "16_16") (pintype "bidirectional"))
      (node (ref "TP47") (pin "P$1") (pinfunction "P$1_P$1") (pintype "bidirectional"))
    )
    (net (code "56") (name "Net-(J7-Pad17)") (class "Default")
      (node (ref "J7") (pin "17") (pinfunction "17_17") (pintype "bidirectional"))
      (node (ref "TP48") (pin "P$1") (pinfunction "P$1_P$1") (pintype "bidirectional"))
    )
    (net (code "57") (name "Net-(J7-Pad18)") (class "Default")
      (node (ref "J7") (pin "18") (pinfunction "18_18") (pintype "bidirectional"))
      (node (ref "TP49") (pin "P$1") (pinfunction "P$1_P$1") (pintype "bidirectional"))
    )
    (net (code "58") (name "Net-(J7-Pad19)") (class "Default")
      (node (ref "J7") (pin "19") (pinfunction "19_19") (pintype "bidirectional"))
      (node (ref "TP50") (pin "P$1") (pinfunction "P$1_P$1") (pintype "bidirectional"))
    )
    (net (code "59") (name "Net-(J8-Pad6)") (class "Default")
      (node (ref "J8") (pin "6") (pinfunction "6_6") (pintype "bidirectional"))
      (node (ref "TP55") (pin "P$1") (pinfunction "P$1_P$1") (pintype "bidirectional"))
    )
    (net (code "60") (name "Net-(J8-Pad7)") (class "Default")
      (node (ref "J8") (pin "7") (pinfunction "7_7") (pintype "bidirectional"))
      (node (ref "TP56") (pin "P$1") (pinfunction "P$1_P$1") (pintype "bidirectional"))
    )
    (net (code "61") (name "Net-(J8-Pad8)") (class "Default")
      (node (ref "J8") (pin "8") (pinfunction "8_8") (pintype "bidirectional"))
      (node (ref "TP57") (pin "P$1") (pinfunction "P$1_P$1") (pintype "bidirectional"))
    )
    (net (code "62") (name "Net-(J8-Pad9)") (class "Default")
      (node (ref "J8") (pin "9") (pinfunction "9_9") (pintype "bidirectional"))
      (node (ref "TP58") (pin "P$1") (pinfunction "P$1_P$1") (pintype "bidirectional"))
    )
    (net (code "63") (name "Net-(J8-Pad12)") (class "Default")
      (node (ref "J8") (pin "12") (pinfunction "12_12") (pintype "bidirectional"))
      (node (ref "TP59") (pin "P$1") (pinfunction "P$1_P$1") (pintype "bidirectional"))
    )
    (net (code "64") (name "Net-(J8-Pad13)") (class "Default")
      (node (ref "J8") (pin "13") (pinfunction "13_13") (pintype "bidirectional"))
      (node (ref "TP60") (pin "P$1") (pinfunction "P$1_P$1") (pintype "bidirectional"))
    )
    (net (code "65") (name "Net-(J8-Pad14)") (class "Default")
      (node (ref "J8") (pin "14") (pinfunction "14_14") (pintype "bidirectional"))
      (node (ref "TP61") (pin "P$1") (pinfunction "P$1_P$1") (pintype "bidirectional"))
    )
    (net (code "66") (name "Net-(J8-Pad15)") (class "Default")
      (node (ref "J8") (pin "15") (pinfunction "15_15") (pintype "bidirectional"))
      (node (ref "TP62") (pin "P$1") (pinfunction "P$1_P$1") (pintype "bidirectional"))
    )
    (net (code "67") (name "Net-(J8-Pad16)") (class "Default")
      (node (ref "J8") (pin "16") (pinfunction "16_16") (pintype "bidirectional"))
      (node (ref "TP63") (pin "P$1") (pinfunction "P$1_P$1") (pintype "bidirectional"))
    )
    (net (code "68") (name "Net-(J8-Pad17)") (class "Default")
      (node (ref "J8") (pin "17") (pinfunction "17_17") (pintype "bidirectional"))
      (node (ref "TP64") (pin "P$1") (pinfunction "P$1_P$1") (pintype "bidirectional"))
    )
    (net (code "69") (name "Net-(J8-Pad18)") (class "Default")
      (node (ref "J8") (pin "18") (pinfunction "18_18") (pintype "bidirectional"))
      (node (ref "TP65") (pin "P$1") (pinfunction "P$1_P$1") (pintype "bidirectional"))
    )
    (net (code "70") (name "Net-(J8-Pad19)") (class "Default")
      (node (ref "J8") (pin "19") (pinfunction "19_19") (pintype "bidirectional"))
      (node (ref "TP66") (pin "P$1") (pinfunction "P$1_P$1") (pintype "bidirectional"))
    )
    (net (code "71") (name "Net-(J9-Pad6)") (class "Default")
      (node (ref "J9") (pin "6") (pinfunction "6_6") (pintype "bidirectional"))
      (node (ref "TP71") (pin "P$1") (pinfunction "P$1_P$1") (pintype "bidirectional"))
    )
    (net (code "72") (name "Net-(J9-Pad7)") (class "Default")
      (node (ref "J9") (pin "7") (pinfunction "7_7") (pintype "bidirectional"))
      (node (ref "TP72") (pin "P$1") (pinfunction "P$1_P$1") (pintype "bidirectional"))
    )
    (net (code "73") (name "Net-(J9-Pad8)") (class "Default")
      (node (ref "J9") (pin "8") (pinfunction "8_8") (pintype "bidirectional"))
      (node (ref "TP73") (pin "P$1") (pinfunction "P$1_P$1") (pintype "bidirectional"))
    )
    (net (code "74") (name "Net-(J9-Pad9)") (class "Default")
      (node (ref "J9") (pin "9") (pinfunction "9_9") (pintype "bidirectional"))
      (node (ref "TP74") (pin "P$1") (pinfunction "P$1_P$1") (pintype "bidirectional"))
    )
    (net (code "75") (name "Net-(J9-Pad12)") (class "Default")
      (node (ref "J9") (pin "12") (pinfunction "12_12") (pintype "bidirectional"))
      (node (ref "TP75") (pin "P$1") (pinfunction "P$1_P$1") (pintype "bidirectional"))
    )
    (net (code "76") (name "Net-(J9-Pad13)") (class "Default")
      (node (ref "J9") (pin "13") (pinfunction "13_13") (pintype "bidirectional"))
      (node (ref "TP76") (pin "P$1") (pinfunction "P$1_P$1") (pintype "bidirectional"))
    )
    (net (code "77") (name "Net-(J9-Pad14)") (class "Default")
      (node (ref "J9") (pin "14") (pinfunction "14_14") (pintype "bidirectional"))
      (node (ref "TP77") (pin "P$1") (pinfunction "P$1_P$1") (pintype "bidirectional"))
    )
    (net (code "78") (name "Net-(J9-Pad15)") (class "Default")
      (node (ref "J9") (pin "15") (pinfunction "15_15") (pintype "bidirectional"))
      (node (ref "TP78") (pin "P$1") (pinfunction "P$1_P$1") (pintype "bidirectional"))
    )
    (net (code "79") (name "Net-(J9-Pad16)") (class "Default")
      (node (ref "J9") (pin "16") (pinfunction "16_16") (pintype "bidirectional"))
      (node (ref "TP79") (pin "P$1") (pinfunction "P$1_P$1") (pintype "bidirectional"))
    )
    (net (code "80") (name "Net-(J9-Pad17)") (class "Default")
      (node (ref "J9") (pin "17") (pinfunction "17_17") (pintype "bidirectional"))
      (node (ref "TP80") (pin "P$1") (pinfunction "P$1_P$1") (pintype "bidirectional"))
    )
    (net (code "81") (name "Net-(J9-Pad18)") (class "Default")
      (node (ref "J9") (pin "18") (pinfunction "18_18") (pintype "bidirectional"))
      (node (ref "TP81") (pin "P$1") (pinfunction "P$1_P$1") (pintype "bidirectional"))
    )
    (net (code "82") (name "Net-(J9-Pad19)") (class "Default")
      (node (ref "J9") (pin "19") (pinfunction "19_19") (pintype "bidirectional"))
      (node (ref "TP82") (pin "P$1") (pinfunction "P$1_P$1") (pintype "bidirectional"))
    )
    (net (code "83") (name "Net-(PP2-P$1)") (class "Default")
      (node (ref "D3") (pin "A") (pinfunction "A_A") (pintype "passive"))
      (node (ref "J2") (pin "1") (pinfunction "1_1") (pintype "power_in"))
      (node (ref "PP2") (pin "1") (pinfunction "P$1_1") (pintype "bidirectional"))
    )
    (net (code "84") (name "Net-(PP3-P$1)") (class "Default")
      (node (ref "D1") (pin "A") (pinfunction "A_A") (pintype "passive"))
      (node (ref "J3") (pin "1") (pinfunction "1_1") (pintype "power_in"))
      (node (ref "PP3") (pin "1") (pinfunction "P$1_1") (pintype "bidirectional"))
    )
    (net (code "85") (name "Net-(PP4-P$1)") (class "Default")
      (node (ref "D4") (pin "A") (pinfunction "A_A") (pintype "passive"))
      (node (ref "J4") (pin "1") (pinfunction "1_1") (pintype "power_in"))
      (node (ref "PP4") (pin "1") (pinfunction "P$1_1") (pintype "bidirectional"))
    )
    (net (code "86") (name "Net-(PP5-P$1)") (class "Default")
      (node (ref "D5") (pin "A") (pinfunction "A_A") (pintype "passive"))
      (node (ref "J5") (pin "1") (pinfunction "1_1") (pintype "power_in"))
      (node (ref "PP5") (pin "1") (pinfunction "P$1_1") (pintype "bidirectional"))
    )
    (net (code "87") (name "Net-(PP7-P$1)") (class "Default")
      (node (ref "J2") (pin "3") (pinfunction "3_3") (pintype "power_in"))
      (node (ref "PP7") (pin "1") (pinfunction "P$1_1") (pintype "bidirectional"))
      (node (ref "R3") (pin "1") (pinfunction "1_1") (pintype "passive"))
      (node (ref "TP2") (pin "P$1") (pinfunction "P$1_P$1") (pintype "bidirectional"))
      (node (ref "TP6") (pin "P$1") (pinfunction "P$1_P$1") (pintype "bidirectional"))
    )
    (net (code "88") (name "Net-(PP8-P$1)") (class "Default")
      (node (ref "J3") (pin "3") (pinfunction "3_3") (pintype "power_in"))
      (node (ref "PP8") (pin "1") (pinfunction "P$1_1") (pintype "bidirectional"))
      (node (ref "R1") (pin "1") (pinfunction "1_1") (pintype "passive"))
      (node (ref "TP3") (pin "P$1") (pinfunction "P$1_P$1") (pintype "bidirectional"))
      (node (ref "TP7") (pin "P$1") (pinfunction "P$1_P$1") (pintype "bidirectional"))
    )
    (net (code "89") (name "Net-(PP9-P$1)") (class "Default")
      (node (ref "J4") (pin "3") (pinfunction "3_3") (pintype "power_in"))
      (node (ref "PP9") (pin "1") (pinfunction "P$1_1") (pintype "bidirectional"))
      (node (ref "R4") (pin "1") (pinfunction "1_1") (pintype "passive"))
      (node (ref "TP4") (pin "P$1") (pinfunction "P$1_P$1") (pintype "bidirectional"))
      (node (ref "TP8") (pin "P$1") (pinfunction "P$1_P$1") (pintype "bidirectional"))
    )
    (net (code "90") (name "Net-(PP10-P$1)") (class "Default")
      (node (ref "J5") (pin "3") (pinfunction "3_3") (pintype "power_in"))
      (node (ref "PP10") (pin "1") (pinfunction "P$1_1") (pintype "bidirectional"))
      (node (ref "R5") (pin "1") (pinfunction "1_1") (pintype "passive"))
      (node (ref "TP5") (pin "P$1") (pinfunction "P$1_P$1") (pintype "bidirectional"))
    )
    (net (code "91") (name "Net-(PP11-P$1)") (class "Default")
      (node (ref "D15") (pin "C") (pinfunction "C_C") (pintype "passive"))
      (node (ref "PP11") (pin "1") (pinfunction "P$1_1") (pintype "bidirectional"))
    )
    (net (code "92") (name "Net-(Q2-PadD)") (class "Default")
      (node (ref "Q2") (pin "D") (pinfunction "D_D") (pintype "passive"))
      (node (ref "R7") (pin "1") (pinfunction "1_1") (pintype "passive"))
      (node (ref "TP9") (pin "P$1") (pinfunction "P$1_P$1") (pintype "bidirectional"))
    )
    (net (code "93") (name "Net-(Q3-PadD)") (class "Default")
      (node (ref "Q3") (pin "D") (pinfunction "D_D") (pintype "passive"))
      (node (ref "R8") (pin "1") (pinfunction "1_1") (pintype "passive"))
      (node (ref "TP10") (pin "P$1") (pinfunction "P$1_P$1") (pintype "bidirectional"))
    )
    (net (code "94") (name "Net-(Q5-PadD)") (class "Default")
      (node (ref "Q5") (pin "D") (pinfunction "D_D") (pintype "passive"))
      (node (ref "R11") (pin "1") (pinfunction "1_1") (pintype "passive"))
      (node (ref "TP11") (pin "P$1") (pinfunction "P$1_P$1") (pintype "bidirectional"))
    )
    (net (code "95") (name "Net-(Q6-PadD)") (class "Default")
      (node (ref "Q6") (pin "D") (pinfunction "D_D") (pintype "passive"))
      (node (ref "R12") (pin "1") (pinfunction "1_1") (pintype "passive"))
      (node (ref "TP12") (pin "P$1") (pinfunction "P$1_P$1") (pintype "bidirectional"))
    )
    (net (code "96") (name "Net-(Q8-PadD)") (class "Default")
      (node (ref "Q8") (pin "D") (pinfunction "D_D") (pintype "passive"))
      (node (ref "R15") (pin "1") (pinfunction "1_1") (pintype "passive"))
      (node (ref "TP13") (pin "P$1") (pinfunction "P$1_P$1") (pintype "bidirectional"))
    )
    (net (code "97") (name "Net-(Q9-PadD)") (class "Default")
      (node (ref "Q9") (pin "D") (pinfunction "D_D") (pintype "passive"))
      (node (ref "R16") (pin "1") (pinfunction "1_1") (pintype "passive"))
      (node (ref "TP14") (pin "P$1") (pinfunction "P$1_P$1") (pintype "bidirectional"))
    )
    (net (code "98") (name "Net-(Q11-PadD)") (class "Default")
      (node (ref "Q11") (pin "D") (pinfunction "D_D") (pintype "passive"))
      (node (ref "R19") (pin "1") (pinfunction "1_1") (pintype "passive"))
      (node (ref "TP15") (pin "P$1") (pinfunction "P$1_P$1") (pintype "bidirectional"))
    )
    (net (code "99") (name "Net-(Q12-PadD)") (class "Default")
      (node (ref "Q12") (pin "D") (pinfunction "D_D") (pintype "passive"))
      (node (ref "R20") (pin "1") (pinfunction "1_1") (pintype "passive"))
      (node (ref "TP16") (pin "P$1") (pinfunction "P$1_P$1") (pintype "bidirectional"))
    )
    (net (code "100") (name "Net-(Q14-PadD)") (class "Default")
      (node (ref "Q14") (pin "D") (pinfunction "D_D") (pintype "passive"))
      (node (ref "R23") (pin "1") (pinfunction "1_1") (pintype "passive"))
      (node (ref "TP17") (pin "P$1") (pinfunction "P$1_P$1") (pintype "bidirectional"))
    )
    (net (code "101") (name "Net-(Q15-PadD)") (class "Default")
      (node (ref "Q15") (pin "D") (pinfunction "D_D") (pintype "passive"))
      (node (ref "R24") (pin "1") (pinfunction "1_1") (pintype "passive"))
      (node (ref "TP18") (pin "P$1") (pinfunction "P$1_P$1") (pintype "bidirectional"))
    )
    (net (code "102") (name "unconnected-(J1-Pad2)") (class "Default")
      (node (ref "J1") (pin "2") (pinfunction "2_2") (pintype "power_in"))
    )
    (net (code "103") (name "unconnected-(J2-Pad2)") (class "Default")
      (node (ref "J2") (pin "2") (pinfunction "2_2") (pintype "power_in"))
    )
    (net (code "104") (name "unconnected-(J3-Pad2)") (class "Default")
      (node (ref "J3") (pin "2") (pinfunction "2_2") (pintype "power_in"))
    )
    (net (code "105") (name "unconnected-(J4-Pad2)") (class "Default")
      (node (ref "J4") (pin "2") (pinfunction "2_2") (pintype "power_in"))
    )
    (net (code "106") (name "unconnected-(J5-Pad2)") (class "Default")
      (node (ref "J5") (pin "2") (pinfunction "2_2") (pintype "power_in"))
    )
  )
)
